# spaceloop_sensor.net
KiCad netlist of a schematic drawn in EAGLE
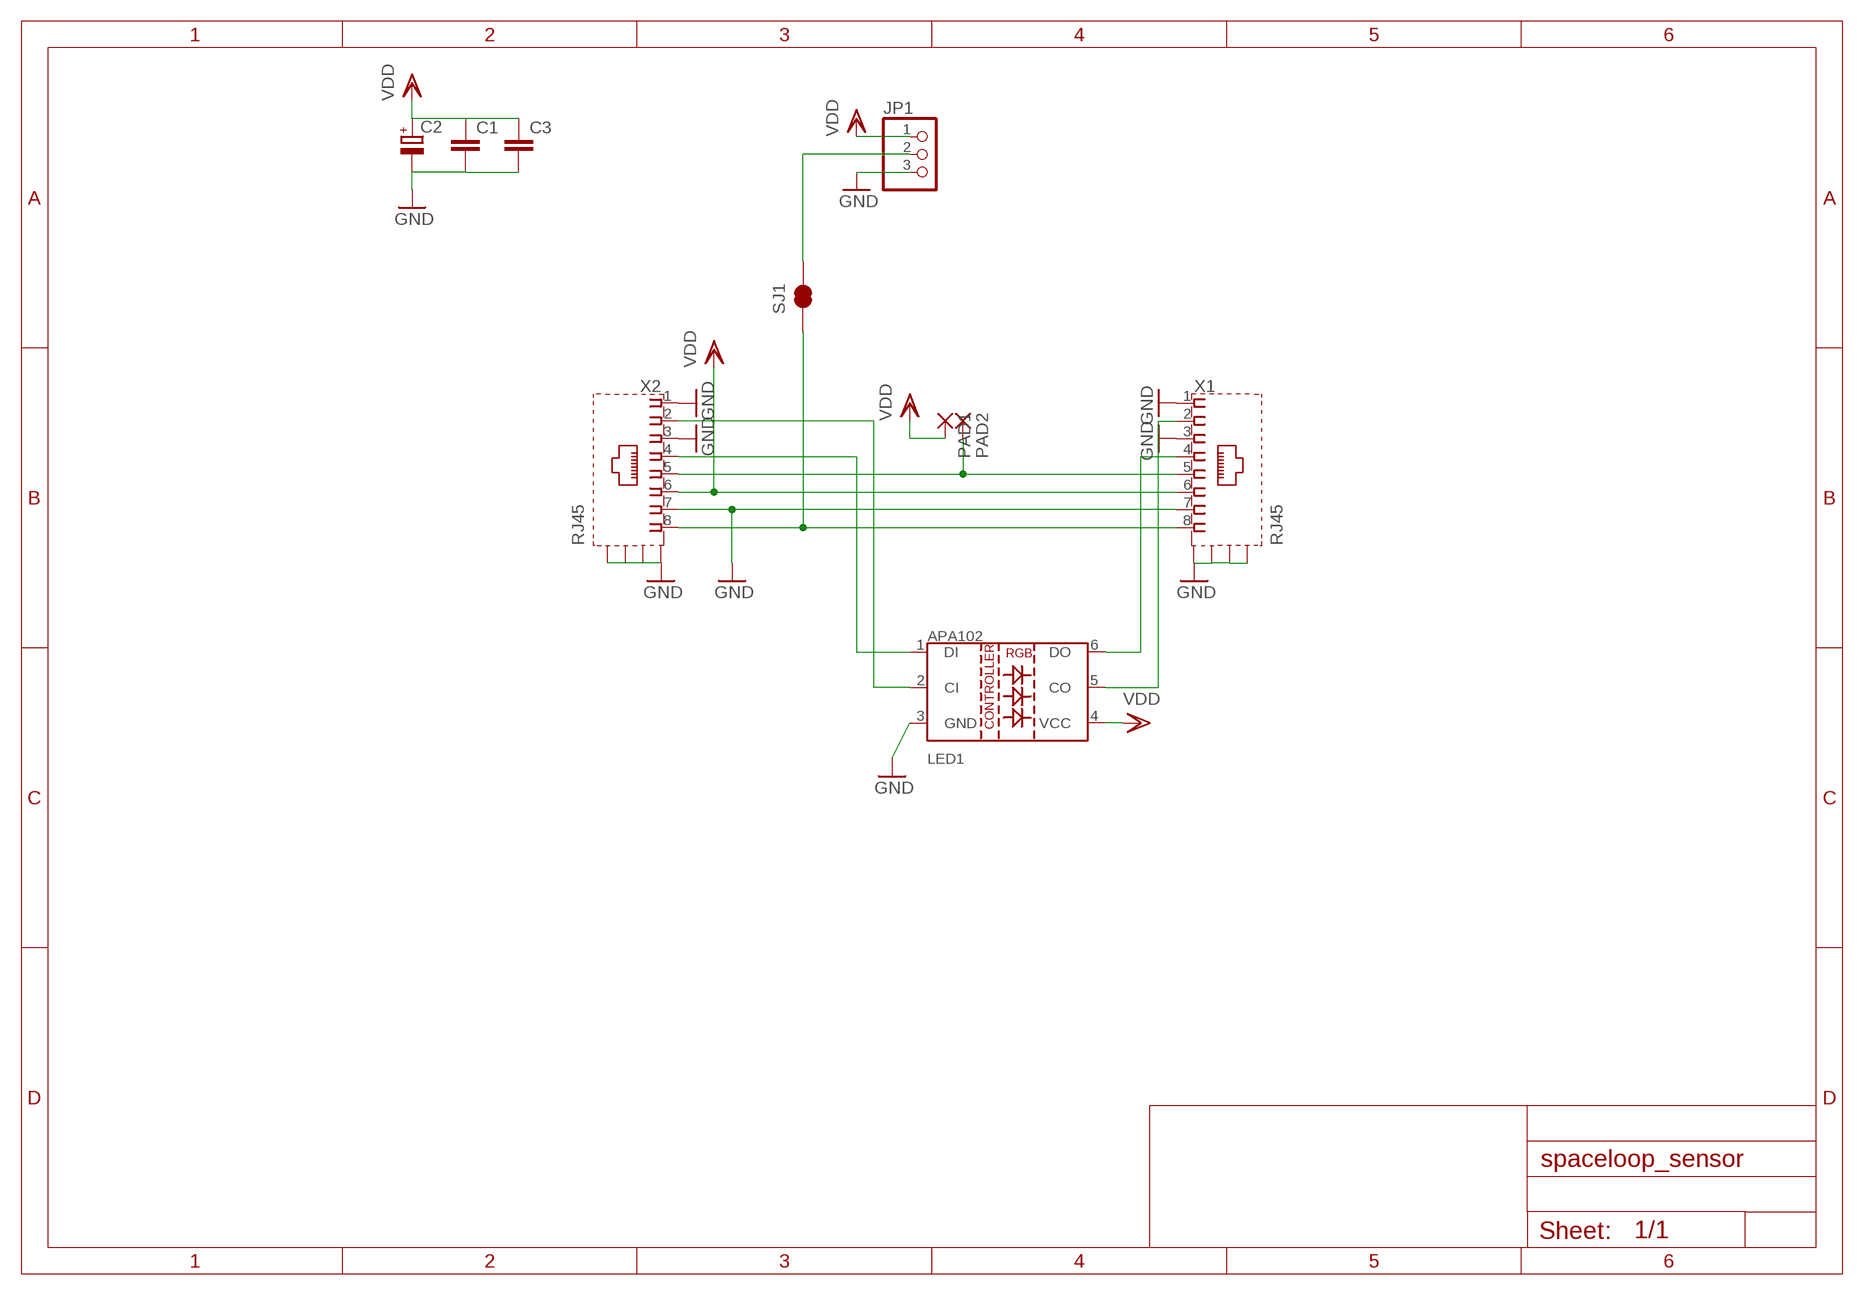
[diagram p0: schematic, sheet 1]

(export (version "E")
  (design (tool "Eeschema 10.0.6"))
  (components
    (comp (ref "C1")
      (value "C-EUC0805K")
      (footprint "eagle-import:C0805K")
      (libsource (lib "eagle-import") (part "C-EUC0805K"))
    )
    (comp (ref "C2")
      (value "CPOL-EU150CLZ-0810")
      (footprint "eagle-import:150CLZ-0810")
      (libsource (lib "eagle-import") (part "CPOL-EU150CLZ-0810"))
    )
    (comp (ref "C3")
      (value "C-EUC0805K")
      (footprint "eagle-import:C0805K")
      (libsource (lib "eagle-import") (part "C-EUC0805K"))
    )
    (comp (ref "JP1")
      (value "PINHD-1X3")
      (footprint "eagle-import:1X03")
      (libsource (lib "eagle-import") (part "PINHD-1X3"))
    )
    (comp (ref "LED1")
      (value "LED-APA102")
      (footprint "eagle-import:LED-APA102")
      (libsource (lib "eagle-import") (part "LED-APA102"))
    )
    (comp (ref "PAD1")
      (value "SMD5")
      (footprint "eagle-import:SMD2,54-5,08")
      (libsource (lib "eagle-import") (part "SMD5"))
    )
    (comp (ref "PAD2")
      (value "SMD5")
      (footprint "eagle-import:SMD2,54-5,08")
      (libsource (lib "eagle-import") (part "SMD5"))
    )
    (comp (ref "SJ1")
      (value "JUMPER-PAD-2-NC_BY_TRACENO_SILK")
      (footprint "eagle-import:PAD-JUMPER-2-NC_BY_TRACE_NO_SILK")
      (libsource (lib "eagle-import") (part "JUMPER-PAD-2-NC_BY_TRACENO_SILK"))
    )
    (comp (ref "X1")
      (value "RJ45")
      (footprint "eagle-import:RJ45-SHIELD2")
      (fields (field (name "MPN") "RJ45-6L2-B"))
      (libsource (lib "eagle-import") (part "RJ452-B-6L"))
    )
    (comp (ref "X2")
      (value "RJ45")
      (footprint "eagle-import:RJ45-SHIELD2")
      (fields (field (name "MPN") "RJ45-6L2-B"))
      (libsource (lib "eagle-import") (part "RJ452-B-6L"))
    )
  )
  (nets
    (net (code "1") (name "GND") (class "Default")
      (node (ref "C1") (pin "2") (pinfunction "2_2") (pintype "passive"))
      (node (ref "C2") (pin "-") (pinfunction "-_-") (pintype "passive"))
      (node (ref "C3") (pin "2") (pinfunction "2_2") (pintype "passive"))
      (node (ref "JP1") (pin "3") (pinfunction "3_3") (pintype "passive"))
      (node (ref "LED1") (pin "3") (pinfunction "GND_3") (pintype "bidirectional"))
      (node (ref "X1") (pin "1") (pinfunction "1_1") (pintype "passive"))
      (node (ref "X1") (pin "3") (pinfunction "3_3") (pintype "passive"))
      (node (ref "X1") (pin "7") (pinfunction "7_7") (pintype "passive"))
      (node (ref "X1") (pin "S1") (pinfunction "S_S1") (pintype "passive"))
      (node (ref "X1") (pin "S2") (pinfunction "S_S2") (pintype "passive"))
      (node (ref "X1") (pin "S3") (pinfunction "S_S3") (pintype "passive"))
      (node (ref "X1") (pin "S4") (pinfunction "S_S4") (pintype "passive"))
      (node (ref "X2") (pin "1") (pinfunction "1_1") (pintype "passive"))
      (node (ref "X2") (pin "3") (pinfunction "3_3") (pintype "passive"))
      (node (ref "X2") (pin "7") (pinfunction "7_7") (pintype "passive"))
      (node (ref "X2") (pin "S1") (pinfunction "S_S1") (pintype "passive"))
      (node (ref "X2") (pin "S2") (pinfunction "S_S2") (pintype "passive"))
      (node (ref "X2") (pin "S3") (pinfunction "S_S3") (pintype "passive"))
      (node (ref "X2") (pin "S4") (pinfunction "S_S4") (pintype "passive"))
    )
    (net (code "2") (name "Net-(JP1-Pad2)") (class "Default")
      (node (ref "JP1") (pin "2") (pinfunction "2_2") (pintype "passive"))
      (node (ref "SJ1") (pin "2") (pinfunction "2_2") (pintype "passive"))
    )
    (net (code "3") (name "Net-(LED1-CI)") (class "Default")
      (node (ref "LED1") (pin "2") (pinfunction "CI_2") (pintype "bidirectional"))
      (node (ref "X2") (pin "2") (pinfunction "2_2") (pintype "passive"))
    )
    (net (code "4") (name "Net-(LED1-CO)") (class "Default")
      (node (ref "LED1") (pin "5") (pinfunction "CO_5") (pintype "bidirectional"))
      (node (ref "X1") (pin "2") (pinfunction "2_2") (pintype "passive"))
    )
    (net (code "5") (name "Net-(LED1-DI)") (class "Default")
      (node (ref "LED1") (pin "1") (pinfunction "DI_1") (pintype "bidirectional"))
      (node (ref "X2") (pin "4") (pinfunction "4_4") (pintype "passive"))
    )
    (net (code "6") (name "Net-(LED1-DO)") (class "Default")
      (node (ref "LED1") (pin "6") (pinfunction "DO_6") (pintype "bidirectional"))
      (node (ref "X1") (pin "4") (pinfunction "4_4") (pintype "passive"))
    )
    (net (code "7") (name "Net-(PAD2-P)") (class "Default")
      (node (ref "PAD2") (pin "1") (pinfunction "P_1") (pintype "passive"))
      (node (ref "X1") (pin "5") (pinfunction "5_5") (pintype "passive"))
      (node (ref "X2") (pin "5") (pinfunction "5_5") (pintype "passive"))
    )
    (net (code "8") (name "Net-(SJ1-Pad1)") (class "Default")
      (node (ref "SJ1") (pin "1") (pinfunction "1_1") (pintype "passive"))
      (node (ref "X1") (pin "8") (pinfunction "8_8") (pintype "passive"))
      (node (ref "X2") (pin "8") (pinfunction "8_8") (pintype "passive"))
    )
    (net (code "9") (name "VDD") (class "Default")
      (node (ref "C1") (pin "1") (pinfunction "1_1") (pintype "passive"))
      (node (ref "C2") (pin "+") (pinfunction "+_+") (pintype "passive"))
      (node (ref "C3") (pin "1") (pinfunction "1_1") (pintype "passive"))
      (node (ref "JP1") (pin "1") (pinfunction "1_1") (pintype "passive"))
      (node (ref "LED1") (pin "4") (pinfunction "VCC_4") (pintype "bidirectional"))
      (node (ref "PAD1") (pin "1") (pinfunction "P_1") (pintype "passive"))
      (node (ref "X1") (pin "6") (pinfunction "6_6") (pintype "passive"))
      (node (ref "X2") (pin "6") (pinfunction "6_6") (pintype "passive"))
    )
  )
)
